# buttons.net
KiCad netlist of a schematic drawn in EAGLE
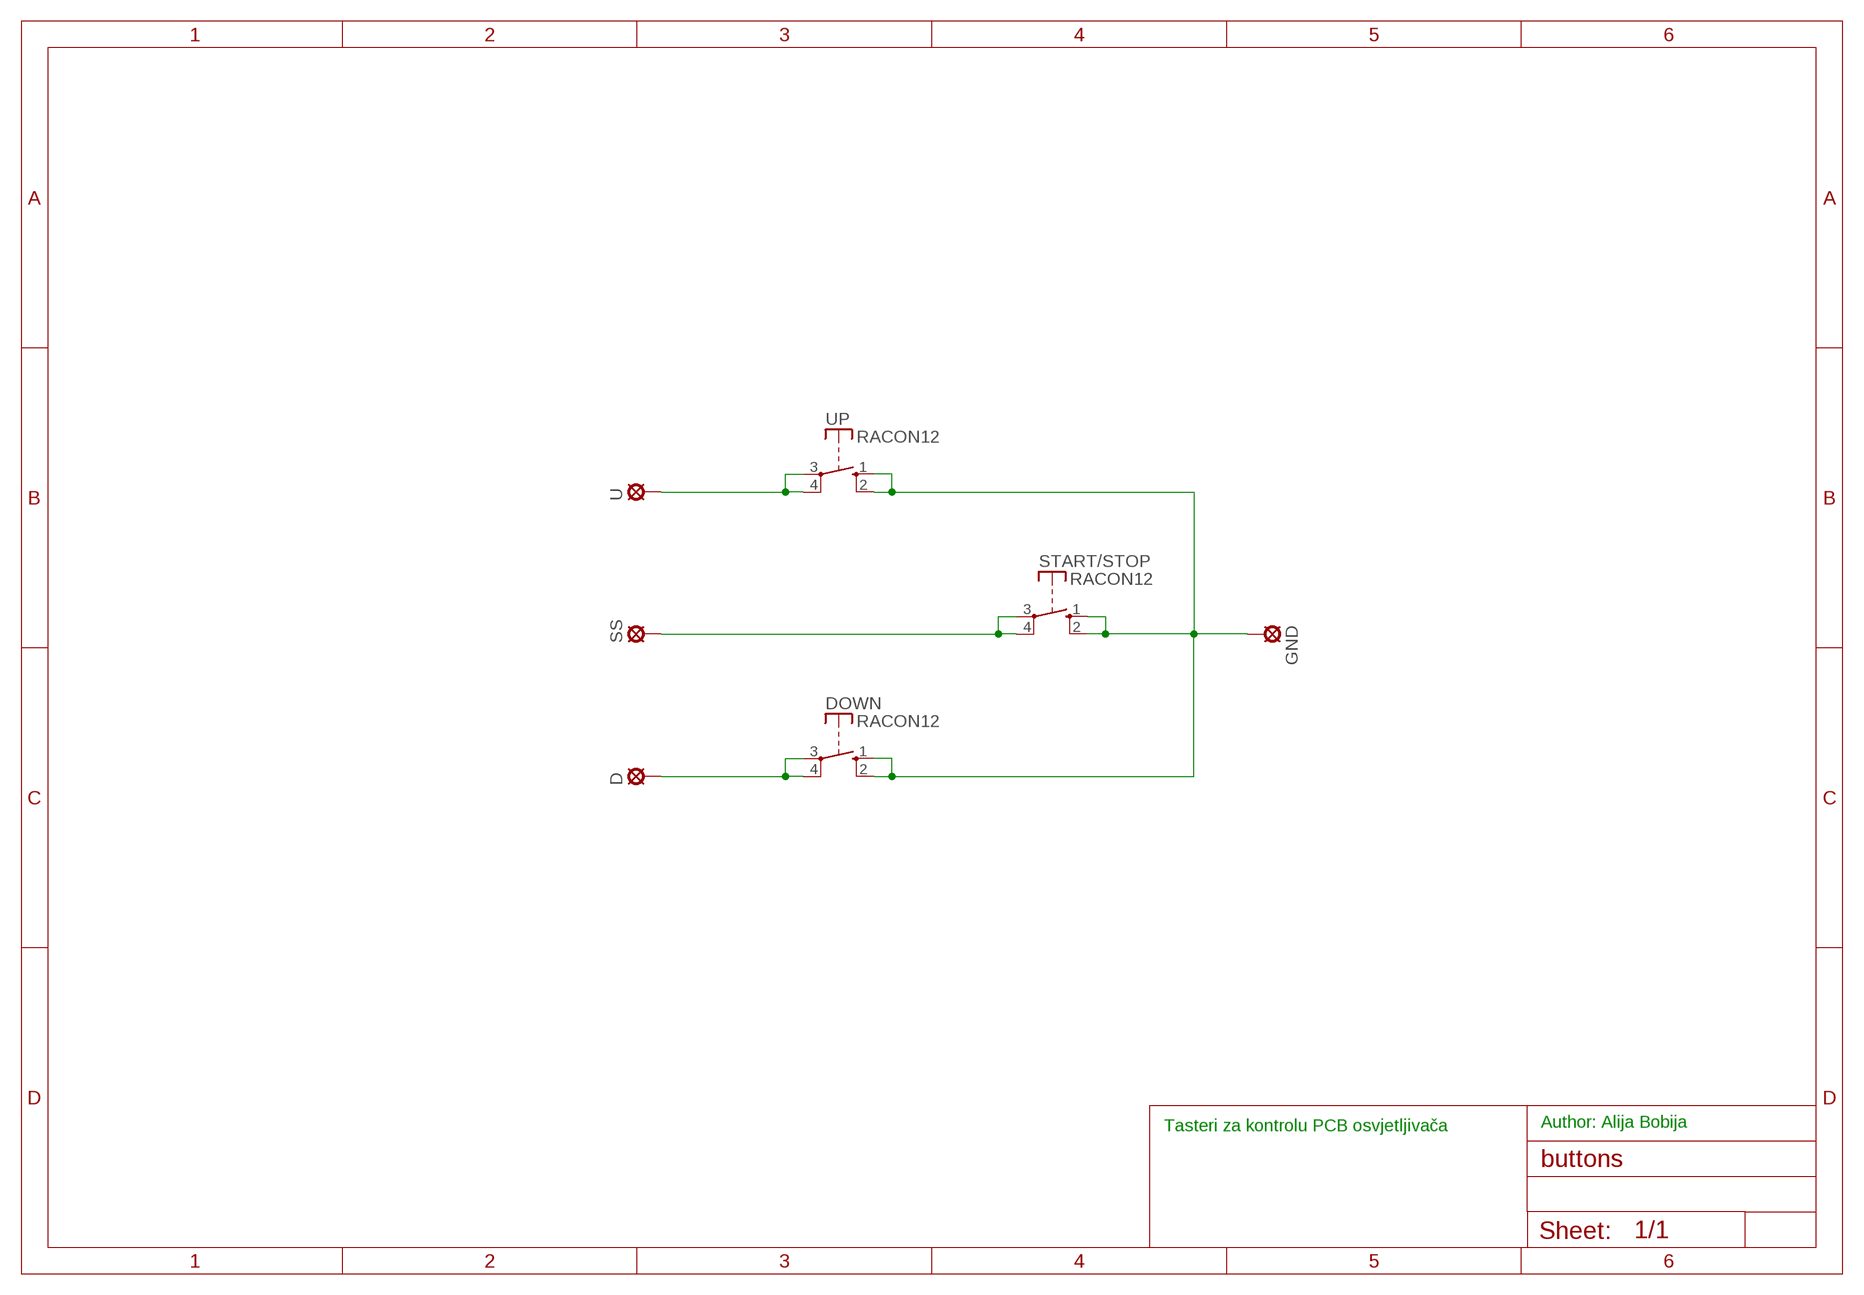
[diagram p0: schematic, sheet 1]

(export (version "E")
  (design (tool "Eeschema 10.0.6"))
  (components
    (comp (ref "D")
      (value "SE11")
      (footprint "eagle-import:SE11")
      (libsource (lib "eagle-import") (part "SE11"))
    )
    (comp (ref "DOWN")
      (value "RACON12")
      (footprint "eagle-import:RACON12")
      (libsource (lib "eagle-import") (part "RACON12"))
    )
    (comp (ref "GND")
      (value "SE11")
      (footprint "eagle-import:SE11")
      (libsource (lib "eagle-import") (part "SE11"))
    )
    (comp (ref "SS")
      (value "SE11")
      (footprint "eagle-import:SE11")
      (libsource (lib "eagle-import") (part "SE11"))
    )
    (comp (ref "START/STOP")
      (value "RACON12")
      (footprint "eagle-import:RACON12")
      (libsource (lib "eagle-import") (part "RACON12"))
    )
    (comp (ref "U")
      (value "SE11")
      (footprint "eagle-import:SE11")
      (libsource (lib "eagle-import") (part "SE11"))
    )
    (comp (ref "UP")
      (value "RACON12")
      (footprint "eagle-import:RACON12")
      (libsource (lib "eagle-import") (part "RACON12"))
    )
  )
  (nets
    (net (code "1") (name "Net-(D-PadMP)") (class "Default")
      (node (ref "D") (pin "MP") (pinfunction "MP_MP") (pintype "passive"))
      (node (ref "DOWN") (pin "3") (pinfunction "P_3") (pintype "passive"))
      (node (ref "DOWN") (pin "4") (pinfunction "P_4") (pintype "passive"))
    )
    (net (code "2") (name "Net-(DOWN-S-Pad1)") (class "Default")
      (node (ref "DOWN") (pin "1") (pinfunction "S_1") (pintype "passive"))
      (node (ref "DOWN") (pin "2") (pinfunction "S_2") (pintype "passive"))
      (node (ref "GND") (pin "MP") (pinfunction "MP_MP") (pintype "passive"))
      (node (ref "START/STOP") (pin "1") (pinfunction "S_1") (pintype "passive"))
      (node (ref "START/STOP") (pin "2") (pinfunction "S_2") (pintype "passive"))
      (node (ref "UP") (pin "1") (pinfunction "S_1") (pintype "passive"))
      (node (ref "UP") (pin "2") (pinfunction "S_2") (pintype "passive"))
    )
    (net (code "3") (name "Net-(SS-PadMP)") (class "Default")
      (node (ref "SS") (pin "MP") (pinfunction "MP_MP") (pintype "passive"))
      (node (ref "START/STOP") (pin "3") (pinfunction "P_3") (pintype "passive"))
      (node (ref "START/STOP") (pin "4") (pinfunction "P_4") (pintype "passive"))
    )
    (net (code "4") (name "Net-(U-PadMP)") (class "Default")
      (node (ref "U") (pin "MP") (pinfunction "MP_MP") (pintype "passive"))
      (node (ref "UP") (pin "3") (pinfunction "P_3") (pintype "passive"))
      (node (ref "UP") (pin "4") (pinfunction "P_4") (pintype "passive"))
    )
  )
)
